# MCU_CU_Schematic.net
KiCad netlist of a schematic drawn in Altium Designer
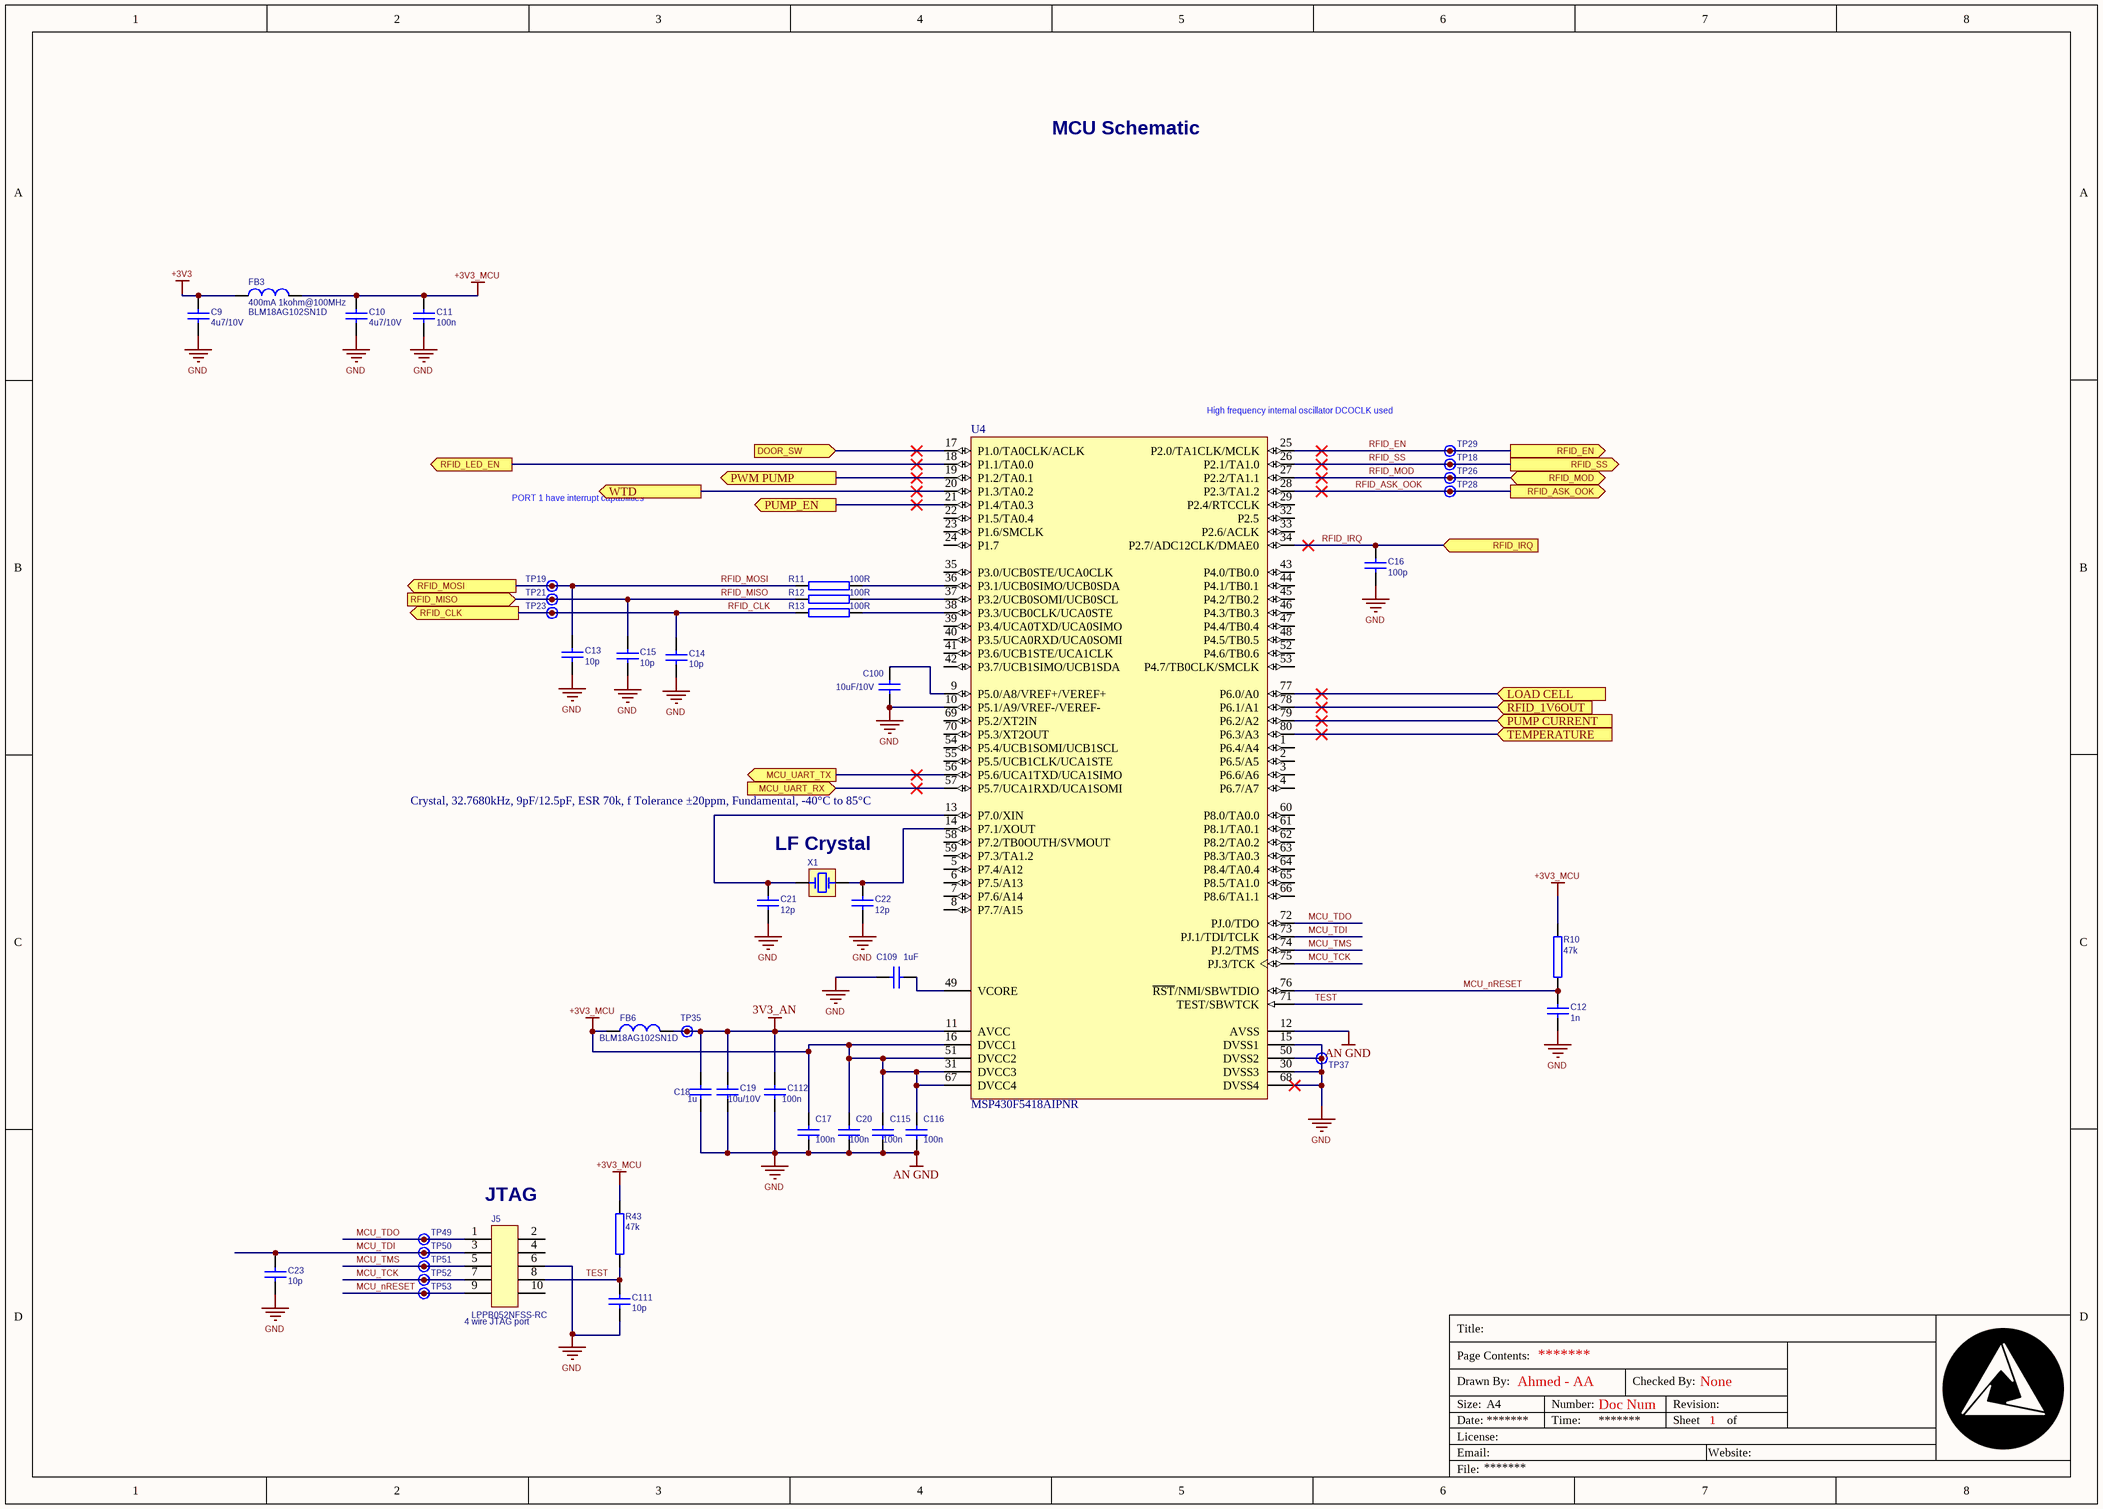
[diagram p0: MCU_CU Schematic.SchDoc]

(export (version "E")
  (design (tool "Eeschema 10.0.6"))
  (components
    (comp (ref "C9")
      (value "4u7/10V")
      (footprint "CAPC1608X09N(0603)")
      (description "Capacitor, Ceramic, 10V, ±10%, X5R, -55°C to 125°C")
      (fields (field (name "02 PART NUMBER") "CC0603KRX5R6BB475") (field (name "12 AUTHOR") "K.Sukumar"))
      (libsource (lib "Ingenuity Master Capacitor Schematic Library") (part "CC0603KRX5R6BB475"))
    )
    (comp (ref "C10")
      (value "4u7/10V")
      (footprint "CAPC1608X09N(0603)")
      (description "Capacitor, Ceramic, 10V, ±10%, X5R, -55°C to 125°C")
      (fields (field (name "02 PART NUMBER") "CC0603KRX5R6BB475") (field (name "12 AUTHOR") "K.Sukumar"))
      (libsource (lib "Ingenuity Master Capacitor Schematic Library") (part "CC0603KRX5R6BB475"))
    )
    (comp (ref "C11")
      (value "100n")
      (footprint "CAPC1608X09N(0603)")
      (description "Capacitor, Ceramic, 50V, ±10%, X7R, -55°C to 125°C")
      (fields (field (name "02 PART NUMBER") "GRM188R71H104KA93D") (field (name "12 AUTHOR") "D.Grace"))
      (libsource (lib "Ingenuity Master Capacitor Schematic Library") (part "GRM188R71H104KA93D"))
    )
    (comp (ref "C12")
      (value "1n")
      (footprint "CAPC1608X09N(0603)")
      (description "Capacitor, Ceramic, 50V, ±5%, C0G NP0, -55°C to 125°C")
      (fields (field (name "02 PART NUMBER") "GRM1885C1H102JA01D") (field (name "12 AUTHOR") "D.Grace"))
      (libsource (lib "Ingenuity Master Capacitor Schematic Library") (part "GRM1885C1H102JA01D"))
    )
    (comp (ref "C13")
      (value "10p")
      (footprint "CAPC1608X09N(0603)")
      (description "Capacitor, Ceramic, 50V, ±5%, NP0, -55°C to 125°C")
      (fields (field (name "02 PART NUMBER") "GQM1885C1H100JB01D") (field (name "12 AUTHOR") "M.Fineschi"))
      (libsource (lib "D0001310 Trophon EPR GUI Carrier Board Schematic Library (1_0)") (part "GQM1885C1H100JB01D"))
    )
    (comp (ref "C14")
      (value "10p")
      (footprint "CAPC1608X09N(0603)")
      (description "Capacitor, Ceramic, 50V, ±5%, NP0, -55°C to 125°C")
      (fields (field (name "02 PART NUMBER") "GQM1885C1H100JB01D") (field (name "12 AUTHOR") "M.Fineschi"))
      (libsource (lib "D0001310 Trophon EPR GUI Carrier Board Schematic Library (1_0)") (part "GQM1885C1H100JB01D"))
    )
    (comp (ref "C15")
      (value "10p")
      (footprint "CAPC1608X09N(0603)")
      (description "Capacitor, Ceramic, 50V, ±5%, NP0, -55°C to 125°C")
      (fields (field (name "02 PART NUMBER") "GQM1885C1H100JB01D") (field (name "12 AUTHOR") "M.Fineschi"))
      (libsource (lib "D0001310 Trophon EPR GUI Carrier Board Schematic Library (1_0)") (part "GQM1885C1H100JB01D"))
    )
    (comp (ref "C16")
      (value "100p")
      (footprint "CAPC1608X09N(0603)")
      (description "Capacitor, Ceramic, 50V, ±5%, C0G NP0, -55°C to 125°C")
      (fields (field (name "02 PART NUMBER") "GRM1885C1H101JA01D") (field (name "12 AUTHOR") "D.Grace"))
      (libsource (lib "Ingenuity Master Capacitor Schematic Library") (part "GRM1885C1H101JA01D"))
    )
    (comp (ref "C17")
      (value "100n")
      (footprint "CAPC1608X09N(0603)")
      (description "Capacitor, Ceramic, 50V, ±10%, X7R, -55°C to 125°C")
      (fields (field (name "02 PART NUMBER") "GRM188R71H104KA93D") (field (name "12 AUTHOR") "D.Grace"))
      (libsource (lib "Ingenuity Master Capacitor Schematic Library") (part "GRM188R71H104KA93D"))
    )
    (comp (ref "C18")
      (value "1u")
      (footprint "CAPC1608X09N(0603)")
      (description "Capacitor, Ceramic, 25V, ±10%, X7R, -55°C to 125°C")
      (fields (field (name "02 PART NUMBER") "GRM188R71E105KA12D") (field (name "12 AUTHOR") "D.Grace"))
      (libsource (lib "Ingenuity Master Capacitor Schematic Library") (part "GRM188R71E105KA12D"))
    )
    (comp (ref "C19")
      (value "10u/10V")
      (footprint "CAPC1608X09N(0603)")
      (description "Capacitor, Ceramic, 10V, ±20%, X5R, -55°C to 85°C")
      (fields (field (name "02 PART NUMBER") "C1608X5R1A106M080AC") (field (name "12 AUTHOR") "K.Sukumar"))
      (libsource (lib "Ingenuity Master Capacitor Schematic Library") (part "C1608X5R1A106M080AC"))
    )
    (comp (ref "C20")
      (value "100n")
      (footprint "CAPC1608X09N(0603)")
      (description "Capacitor, Ceramic, 50V, ±10%, X7R, -55°C to 125°C")
      (fields (field (name "02 PART NUMBER") "GRM188R71H104KA93D") (field (name "12 AUTHOR") "D.Grace"))
      (libsource (lib "Ingenuity Master Capacitor Schematic Library") (part "GRM188R71H104KA93D"))
    )
    (comp (ref "C21")
      (value "12p")
      (footprint "CAPC1608X09N(0603)")
      (description "Capacitor, Ceramic, 50V, ±5%, C0G NP0, -55°C to 125°C")
      (fields (field (name "02 PART NUMBER") "GRM1885C1H120JA01D") (field (name "12 AUTHOR") "D.Grace"))
      (libsource (lib "<Company> Vault") (part "CMP-007-0078-1"))
    )
    (comp (ref "C22")
      (value "12p")
      (footprint "CAPC1608X09N(0603)")
      (description "Capacitor, Ceramic, 50V, ±5%, C0G NP0, -55°C to 125°C")
      (fields (field (name "02 PART NUMBER") "GRM1885C1H120JA01D") (field (name "12 AUTHOR") "D.Grace"))
      (libsource (lib "<Company> Vault") (part "CMP-007-0078-1"))
    )
    (comp (ref "C23")
      (value "10p")
      (footprint "CAPC1608X09N(0603)")
      (description "Capacitor, Ceramic, 50V, ±5%, NP0, -55°C to 125°C")
      (fields (field (name "02 PART NUMBER") "GQM1885C1H100JB01D") (field (name "12 AUTHOR") "M.Fineschi"))
      (libsource (lib "D0001310 Trophon EPR GUI Carrier Board Schematic Library (1_0)") (part "GQM1885C1H100JB01D"))
    )
    (comp (ref "C100")
      (value "10uF/10V")
      (footprint "CAPC1608X09N(0603)")
      (description "Capacitor, Ceramic, 10V, ±10%, X5R, -55°C to 125°C")
      (fields (field (name "02 PART NUMBER") "CC0603KRX5R6BB475") (field (name "12 AUTHOR") "K.Sukumar"))
      (libsource (lib "RFID Board") (part "CC0603KRX5R6BB475"))
    )
    (comp (ref "C109")
      (value "1uF")
      (footprint "CAPC1608X09N(0603)")
      (description "Capacitor, Ceramic, 10V, ±10%, X5R, -55°C to 125°C")
      (fields (field (name "02 PART NUMBER") "CC0603KRX5R6BB475") (field (name "12 AUTHOR") "K.Sukumar"))
      (libsource (lib "RFID Board") (part "CC0603KRX5R6BB475"))
    )
    (comp (ref "C111")
      (value "10p")
      (footprint "CAPC1608X09N(0603)")
      (description "Capacitor, Ceramic, 50V, ±5%, NP0, -55°C to 125°C")
      (fields (field (name "02 PART NUMBER") "GQM1885C1H100JB01D") (field (name "12 AUTHOR") "M.Fineschi"))
      (libsource (lib "D0001310 Trophon EPR GUI Carrier Board Schematic Library (1_0)") (part "GQM1885C1H100JB01D"))
    )
    (comp (ref "C112")
      (value "100n")
      (footprint "CAPC1608X09N(0603)")
      (description "Capacitor, Ceramic, 50V, ±10%, X7R, -55°C to 125°C")
      (fields (field (name "02 PART NUMBER") "GRM188R71H104KA93D") (field (name "12 AUTHOR") "D.Grace"))
      (libsource (lib "Ingenuity Master Capacitor Schematic Library") (part "GRM188R71H104KA93D"))
    )
    (comp (ref "C115")
      (value "100n")
      (footprint "CAPC1608X09N(0603)")
      (description "Capacitor, Ceramic, 50V, ±10%, X7R, -55°C to 125°C")
      (fields (field (name "02 PART NUMBER") "GRM188R71H104KA93D") (field (name "12 AUTHOR") "D.Grace"))
      (libsource (lib "Ingenuity Master Capacitor Schematic Library") (part "GRM188R71H104KA93D"))
    )
    (comp (ref "C116")
      (value "100n")
      (footprint "CAPC1608X09N(0603)")
      (description "Capacitor, Ceramic, 50V, ±10%, X7R, -55°C to 125°C")
      (fields (field (name "02 PART NUMBER") "GRM188R71H104KA93D") (field (name "12 AUTHOR") "D.Grace"))
      (libsource (lib "Ingenuity Master Capacitor Schematic Library") (part "GRM188R71H104KA93D"))
    )
    (comp (ref "FB3")
      (value "400mA 1kohm@100MHz")
      (footprint "RESC1608X06N")
      (description "Ferrite Bead, 1kohm@100MHz, 400mA, 500mohm, -55 to 125C")
      (fields (field (name "02 PART NUMBER") "BLM18AG102SN1D") (field (name "12 AUTHOR") "M.Fineschi"))
      (libsource (lib "D0000174 Puck Charger Schematic Library (1_6)") (part "BLM18AG102SN1D"))
    )
    (comp (ref "FB6")
      (value "400mA 1kohm@100MHz")
      (footprint "RESC1608X06N")
      (description "Ferrite Bead, 1kohm@100MHz, 400mA, 500mohm, -55 to 125C")
      (fields (field (name "02 PART NUMBER") "BLM18AG102SN1D") (field (name "12 AUTHOR") "M.Fineschi"))
      (libsource (lib "D0000174 Puck Charger Schematic Library (1_6)") (part "BLM18AG102SN1D"))
    )
    (comp (ref "J5")
      (value "LPPB052NFSS-RC")
      (footprint "2x 5, 1.27mm Pitch")
      (description "Socket,  Female, 2x5, 10 POS, Pitch 1.27mm")
      (fields (field (name "12 AUTHOR") "K.Sukumar"))
      (libsource (lib "VSS Windscreen Unit Schematic library") (part "LPPB052NFSS-RC"))
    )
    (comp (ref "R10")
      (value "47k")
      (footprint "RESC1608X06N(0603)")
      (description "Resistor, Thick Film, 0.1W, ±1%, ±100ppm/°C")
      (fields
        (field (name "02 PART NUMBER") "RC0603FR-0747KL")
        (field (name "13 REVIEWED BY") "P.Moutzouris")
        (field (name "12 AUTHOR") "D.Grace")
      )
      (libsource (lib "Ingenuity Master Resistor 0603 Schematic Library") (part "RC0603FR-0747KL"))
    )
    (comp (ref "R11")
      (value "100R")
      (footprint "RESC1608X06N(0603)")
      (description "Resistor, Thick Film, 0.1W, ±1%, ±100ppm/°C")
      (fields
        (field (name "02 PART NUMBER") "RC0603FR-07100RL")
        (field (name "13 REVIEWED BY") "P.Moutzouris")
        (field (name "12 AUTHOR") "D.Grace")
      )
      (libsource (lib "Ingenuity Master Resistor 0603 Schematic Library") (part "RC0603FR-07100RL"))
    )
    (comp (ref "R12")
      (value "100R")
      (footprint "RESC1608X06N(0603)")
      (description "Resistor, Thick Film, 0.1W, ±1%, ±100ppm/°C")
      (fields
        (field (name "02 PART NUMBER") "RC0603FR-07100RL")
        (field (name "13 REVIEWED BY") "P.Moutzouris")
        (field (name "12 AUTHOR") "D.Grace")
      )
      (libsource (lib "Ingenuity Master Resistor 0603 Schematic Library") (part "RC0603FR-07100RL"))
    )
    (comp (ref "R13")
      (value "100R")
      (footprint "RESC1608X06N(0603)")
      (description "Resistor, Thick Film, 0.1W, ±1%, ±100ppm/°C")
      (fields
        (field (name "02 PART NUMBER") "RC0603FR-07100RL")
        (field (name "13 REVIEWED BY") "P.Moutzouris")
        (field (name "12 AUTHOR") "D.Grace")
      )
      (libsource (lib "Ingenuity Master Resistor 0603 Schematic Library") (part "RC0603FR-07100RL"))
    )
    (comp (ref "R43")
      (value "47k")
      (footprint "RESC1608X06N(0603)")
      (description "Resistor, Thick Film, 0.1W, ±1%, ±100ppm/°C")
      (fields
        (field (name "02 PART NUMBER") "RC0603FR-0747KL")
        (field (name "13 REVIEWED BY") "P.Moutzouris")
        (field (name "12 AUTHOR") "D.Grace")
      )
      (libsource (lib "Ingenuity Master Resistor 0603 Schematic Library") (part "RC0603FR-0747KL"))
    )
    (comp (ref "TP18")
      (value "LFX_P")
      (footprint "Test Point 1mm")
      (description "Test Point")
      (fields (field (name "12 AUTHOR") "D.Grace"))
      (libsource (lib "Mesh Nebuliser Schematic Library") (part "Test Point"))
    )
    (comp (ref "TP19")
      (value "LFX_P")
      (footprint "Test Point 1mm")
      (description "Test Point")
      (fields (field (name "12 AUTHOR") "D.Grace"))
      (libsource (lib "Mesh Nebuliser Schematic Library") (part "Test Point"))
    )
    (comp (ref "TP21")
      (value "LFX_P")
      (footprint "Test Point 1mm")
      (description "Test Point")
      (fields (field (name "12 AUTHOR") "D.Grace"))
      (libsource (lib "Mesh Nebuliser Schematic Library") (part "Test Point"))
    )
    (comp (ref "TP23")
      (value "LFX_P")
      (footprint "Test Point 1mm")
      (description "Test Point")
      (fields (field (name "12 AUTHOR") "D.Grace"))
      (libsource (lib "Mesh Nebuliser Schematic Library") (part "Test Point"))
    )
    (comp (ref "TP26")
      (value "LFX_P")
      (footprint "Test Point 1mm")
      (description "Test Point")
      (fields (field (name "12 AUTHOR") "D.Grace"))
      (libsource (lib "Mesh Nebuliser Schematic Library") (part "Test Point"))
    )
    (comp (ref "TP28")
      (value "LFX_P")
      (footprint "Test Point 1mm")
      (description "Test Point")
      (fields (field (name "12 AUTHOR") "D.Grace"))
      (libsource (lib "Mesh Nebuliser Schematic Library") (part "Test Point"))
    )
    (comp (ref "TP29")
      (value "LFX_P")
      (footprint "Test Point 1mm")
      (description "Test Point")
      (fields (field (name "12 AUTHOR") "D.Grace"))
      (libsource (lib "Mesh Nebuliser Schematic Library") (part "Test Point"))
    )
    (comp (ref "TP35")
      (value "LFX_P")
      (footprint "Test Point 1mm")
      (description "Test Point")
      (fields (field (name "12 AUTHOR") "D.Grace"))
      (libsource (lib "Mesh Nebuliser Schematic Library") (part "Test Point"))
    )
    (comp (ref "TP37")
      (value "LFX_P")
      (footprint "Test Point 1mm")
      (description "Test Point")
      (fields (field (name "12 AUTHOR") "D.Grace"))
      (libsource (lib "Mesh Nebuliser Schematic Library") (part "Test Point"))
    )
    (comp (ref "TP49")
      (value "TDO")
      (footprint "Test Point 1mm")
      (description "Test Point")
      (fields (field (name "12 AUTHOR") "D.Grace"))
      (libsource (lib "Mesh Nebuliser Schematic Library") (part "Test Point"))
    )
    (comp (ref "TP50")
      (value "TDO")
      (footprint "Test Point 1mm")
      (description "Test Point")
      (fields (field (name "12 AUTHOR") "D.Grace"))
      (libsource (lib "Mesh Nebuliser Schematic Library") (part "Test Point"))
    )
    (comp (ref "TP51")
      (value "TDO")
      (footprint "Test Point 1mm")
      (description "Test Point")
      (fields (field (name "12 AUTHOR") "D.Grace"))
      (libsource (lib "Mesh Nebuliser Schematic Library") (part "Test Point"))
    )
    (comp (ref "TP52")
      (value "TDO")
      (footprint "Test Point 1mm")
      (description "Test Point")
      (fields (field (name "12 AUTHOR") "D.Grace"))
      (libsource (lib "Mesh Nebuliser Schematic Library") (part "Test Point"))
    )
    (comp (ref "TP53")
      (value "TDO")
      (footprint "Test Point 1mm")
      (description "Test Point")
      (fields (field (name "12 AUTHOR") "D.Grace"))
      (libsource (lib "Mesh Nebuliser Schematic Library") (part "Test Point"))
    )
    (comp (ref "U4")
      (value "MSP430F5418AIPNR")
      (footprint "PN0080A_L")
      (fields (field (name "MANUFACTURER") "Texas Instruments"))
      (libsource (lib "Altium Content Vault") (part "CMP-0365-00449-2"))
    )
    (comp (ref "X1")
      (value "CM315D32768DZCT")
      (footprint "CM315D32768DZCT")
      (description "Crystal, 32.7680kHz, 9pF/12.5pF, ESR 70k, f Tolerance ±20ppm, Fundamental, -40°C to 85°C")
      (fields
        (field (name "03 DESCRIPTION") "Crystal, 32.7680kHz, 9pF/12.5pF, ESR 70k, f Tolerance ±20ppm, Fundamental, -40°C to 85°C")
        (field (name "12 AUTHOR") "D.Grace")
      )
      (libsource (lib "<Company> Vault") (part "CMP-007-0044-1"))
    )
  )
  (nets
    (net (code "1") (name "+3V3") (class "Default")
      (node (ref "C9") (pin "2") (pinfunction "2_2") (pintype "passive"))
      (node (ref "FB3") (pin "1") (pinfunction "1_1") (pintype "passive"))
    )
    (net (code "2") (name "+3V3_MCU") (class "Default")
      (node (ref "C10") (pin "2") (pinfunction "2_2") (pintype "passive"))
      (node (ref "C11") (pin "2") (pinfunction "2_2") (pintype "passive"))
      (node (ref "C115") (pin "2") (pinfunction "2_2") (pintype "passive"))
      (node (ref "C116") (pin "2") (pinfunction "2_2") (pintype "passive"))
      (node (ref "C17") (pin "2") (pinfunction "2_2") (pintype "passive"))
      (node (ref "C20") (pin "2") (pinfunction "2_2") (pintype "passive"))
      (node (ref "FB3") (pin "2") (pinfunction "2_2") (pintype "passive"))
      (node (ref "FB6") (pin "1") (pinfunction "1_1") (pintype "passive"))
      (node (ref "R10") (pin "1") (pintype "passive"))
      (node (ref "R43") (pin "1") (pintype "passive"))
      (node (ref "U4") (pin "16") (pinfunction "DVCC1_16") (pintype "power_in"))
      (node (ref "U4") (pin "31") (pinfunction "DVCC3_31") (pintype "power_in"))
      (node (ref "U4") (pin "51") (pinfunction "DVCC2_51") (pintype "power_in"))
      (node (ref "U4") (pin "67") (pinfunction "DVCC4_67") (pintype "power_in"))
    )
    (net (code "3") (name "/DOOR_SW") (class "Default")
      (node (ref "U4") (pin "17") (pinfunction "P1.0/TA0CLK/ACLK_17") (pintype "bidirectional"))
    )
    (net (code "4") (name "/LOAD CELL") (class "Default")
      (node (ref "U4") (pin "77") (pinfunction "P6.0/A0_77") (pintype "bidirectional"))
    )
    (net (code "5") (name "/MCU_TCK") (class "Default")
      (node (ref "J5") (pin "7") (pinfunction "7_7") (pintype "passive"))
      (node (ref "TP52") (pin "TP") (pinfunction "TP_TP") (pintype "passive"))
      (node (ref "U4") (pin "75") (pinfunction "PJ.3/TCK_75") (pintype "bidirectional"))
    )
    (net (code "6") (name "/MCU_TDI") (class "Default")
      (node (ref "C23") (pin "1") (pinfunction "1_1") (pintype "passive"))
      (node (ref "J5") (pin "3") (pinfunction "3_3") (pintype "passive"))
      (node (ref "TP50") (pin "TP") (pinfunction "TP_TP") (pintype "passive"))
      (node (ref "U4") (pin "73") (pinfunction "PJ.1/TDI/TCLK_73") (pintype "bidirectional"))
    )
    (net (code "7") (name "/MCU_TDO") (class "Default")
      (node (ref "J5") (pin "1") (pinfunction "1_1") (pintype "passive"))
      (node (ref "TP49") (pin "TP") (pinfunction "TP_TP") (pintype "passive"))
      (node (ref "U4") (pin "72") (pinfunction "PJ.0/TDO_72") (pintype "bidirectional"))
    )
    (net (code "8") (name "/MCU_TMS") (class "Default")
      (node (ref "J5") (pin "5") (pinfunction "5_5") (pintype "passive"))
      (node (ref "TP51") (pin "TP") (pinfunction "TP_TP") (pintype "passive"))
      (node (ref "U4") (pin "74") (pinfunction "PJ.2/TMS_74") (pintype "bidirectional"))
    )
    (net (code "9") (name "/MCU_UART_RX") (class "Default")
      (node (ref "U4") (pin "57") (pinfunction "P5.7/UCA1RXD/UCA1SOMI_57") (pintype "bidirectional"))
    )
    (net (code "10") (name "/MCU_UART_TX") (class "Default")
      (node (ref "U4") (pin "56") (pinfunction "P5.6/UCA1TXD/UCA1SIMO_56") (pintype "bidirectional"))
    )
    (net (code "11") (name "/MCU_nRESET") (class "Default")
      (node (ref "C12") (pin "2") (pinfunction "2_2") (pintype "passive"))
      (node (ref "J5") (pin "9") (pinfunction "9_9") (pintype "passive"))
      (node (ref "R10") (pin "2") (pintype "passive"))
      (node (ref "TP53") (pin "TP") (pinfunction "TP_TP") (pintype "passive"))
      (node (ref "U4") (pin "76") (pinfunction "~{RST}/NMI/SBWTDIO_76") (pintype "bidirectional"))
    )
    (net (code "12") (name "/PUMP CURRENT") (class "Default")
      (node (ref "U4") (pin "79") (pinfunction "P6.2/A2_79") (pintype "bidirectional"))
    )
    (net (code "13") (name "/PUMP_EN") (class "Default")
      (node (ref "U4") (pin "21") (pinfunction "P1.4/TA0.3_21") (pintype "bidirectional"))
    )
    (net (code "14") (name "/PWM PUMP") (class "Default")
      (node (ref "U4") (pin "19") (pinfunction "P1.2/TA0.1_19") (pintype "bidirectional"))
    )
    (net (code "15") (name "/RFID_1V6OUT") (class "Default")
      (node (ref "U4") (pin "78") (pinfunction "P6.1/A1_78") (pintype "bidirectional"))
    )
    (net (code "16") (name "/RFID_ASK_OOK") (class "Default")
      (node (ref "TP28") (pin "TP") (pinfunction "TP_TP") (pintype "passive"))
      (node (ref "U4") (pin "28") (pinfunction "P2.3/TA1.2_28") (pintype "bidirectional"))
    )
    (net (code "17") (name "/RFID_CLK") (class "Default")
      (node (ref "C14") (pin "1") (pinfunction "1_1") (pintype "passive"))
      (node (ref "R13") (pin "2") (pintype "passive"))
      (node (ref "TP23") (pin "TP") (pinfunction "TP_TP") (pintype "passive"))
    )
    (net (code "18") (name "/RFID_EN") (class "Default")
      (node (ref "TP29") (pin "TP") (pinfunction "TP_TP") (pintype "passive"))
      (node (ref "U4") (pin "25") (pinfunction "P2.0/TA1CLK/MCLK_25") (pintype "bidirectional"))
    )
    (net (code "19") (name "/RFID_IRQ") (class "Default")
      (node (ref "C16") (pin "2") (pinfunction "2_2") (pintype "passive"))
      (node (ref "U4") (pin "34") (pinfunction "P2.7/ADC12CLK/DMAE0_34") (pintype "bidirectional"))
    )
    (net (code "20") (name "/RFID_LED_EN") (class "Default")
      (node (ref "U4") (pin "18") (pinfunction "P1.1/TA0.0_18") (pintype "bidirectional"))
    )
    (net (code "21") (name "/RFID_MISO") (class "Default")
      (node (ref "C15") (pin "1") (pinfunction "1_1") (pintype "passive"))
      (node (ref "R12") (pin "2") (pintype "passive"))
      (node (ref "TP21") (pin "TP") (pinfunction "TP_TP") (pintype "passive"))
    )
    (net (code "22") (name "/RFID_MOD") (class "Default")
      (node (ref "TP26") (pin "TP") (pinfunction "TP_TP") (pintype "passive"))
      (node (ref "U4") (pin "27") (pinfunction "P2.2/TA1.1_27") (pintype "bidirectional"))
    )
    (net (code "23") (name "/RFID_MOSI") (class "Default")
      (node (ref "C13") (pin "1") (pinfunction "1_1") (pintype "passive"))
      (node (ref "R11") (pin "2") (pintype "passive"))
      (node (ref "TP19") (pin "TP") (pinfunction "TP_TP") (pintype "passive"))
    )
    (net (code "24") (name "/RFID_SS") (class "Default")
      (node (ref "TP18") (pin "TP") (pinfunction "TP_TP") (pintype "passive"))
      (node (ref "U4") (pin "26") (pinfunction "P2.1/TA1.0_26") (pintype "bidirectional"))
    )
    (net (code "25") (name "/TEMPERATURE") (class "Default")
      (node (ref "U4") (pin "80") (pinfunction "P6.3/A3_80") (pintype "bidirectional"))
    )
    (net (code "26") (name "/TEST") (class "Default")
      (node (ref "C111") (pin "1") (pinfunction "1_1") (pintype "passive"))
      (node (ref "J5") (pin "8") (pinfunction "8_8") (pintype "passive"))
      (node (ref "R43") (pin "2") (pintype "passive"))
      (node (ref "U4") (pin "71") (pinfunction "TEST/SBWTCK_71") (pintype "input"))
    )
    (net (code "27") (name "/WTD") (class "Default")
      (node (ref "U4") (pin "20") (pinfunction "P1.3/TA0.2_20") (pintype "bidirectional"))
    )
    (net (code "28") (name "3V3_AN") (class "Default")
      (node (ref "C112") (pin "2") (pinfunction "2_2") (pintype "passive"))
      (node (ref "C18") (pin "2") (pinfunction "2_2") (pintype "passive"))
      (node (ref "C19") (pin "2") (pinfunction "2_2") (pintype "passive"))
      (node (ref "FB6") (pin "2") (pinfunction "2_2") (pintype "passive"))
      (node (ref "TP35") (pin "TP") (pinfunction "TP_TP") (pintype "passive"))
      (node (ref "U4") (pin "11") (pinfunction "AVCC_11") (pintype "power_in"))
    )
    (net (code "29") (name "AN GND") (class "Default")
      (node (ref "C10") (pin "1") (pinfunction "1_1") (pintype "passive"))
      (node (ref "C100") (pin "1") (pinfunction "1_1") (pintype "passive"))
      (node (ref "C109") (pin "2") (pinfunction "2_2") (pintype "passive"))
      (node (ref "C11") (pin "1") (pinfunction "1_1") (pintype "passive"))
      (node (ref "C111") (pin "2") (pinfunction "2_2") (pintype "passive"))
      (node (ref "C112") (pin "1") (pinfunction "1_1") (pintype "passive"))
      (node (ref "C115") (pin "1") (pinfunction "1_1") (pintype "passive"))
      (node (ref "C116") (pin "1") (pinfunction "1_1") (pintype "passive"))
      (node (ref "C12") (pin "1") (pinfunction "1_1") (pintype "passive"))
      (node (ref "C13") (pin "2") (pinfunction "2_2") (pintype "passive"))
      (node (ref "C14") (pin "2") (pinfunction "2_2") (pintype "passive"))
      (node (ref "C15") (pin "2") (pinfunction "2_2") (pintype "passive"))
      (node (ref "C16") (pin "1") (pinfunction "1_1") (pintype "passive"))
      (node (ref "C17") (pin "1") (pinfunction "1_1") (pintype "passive"))
      (node (ref "C18") (pin "1") (pinfunction "1_1") (pintype "passive"))
      (node (ref "C19") (pin "1") (pinfunction "1_1") (pintype "passive"))
      (node (ref "C20") (pin "1") (pinfunction "1_1") (pintype "passive"))
      (node (ref "C21") (pin "1") (pinfunction "1_1") (pintype "passive"))
      (node (ref "C22") (pin "1") (pinfunction "1_1") (pintype "passive"))
      (node (ref "C23") (pin "2") (pinfunction "2_2") (pintype "passive"))
      (node (ref "C9") (pin "1") (pinfunction "1_1") (pintype "passive"))
      (node (ref "J5") (pin "6") (pinfunction "6_6") (pintype "passive"))
      (node (ref "TP37") (pin "TP") (pinfunction "TP_TP") (pintype "passive"))
      (node (ref "U4") (pin "10") (pinfunction "P5.1/A9/VREF-/VEREF-_10") (pintype "bidirectional"))
      (node (ref "U4") (pin "12") (pinfunction "AVSS_12") (pintype "power_in"))
      (node (ref "U4") (pin "15") (pinfunction "DVSS1_15") (pintype "power_in"))
      (node (ref "U4") (pin "30") (pinfunction "DVSS3_30") (pintype "power_in"))
      (node (ref "U4") (pin "50") (pinfunction "DVSS2_50") (pintype "power_in"))
      (node (ref "U4") (pin "68") (pinfunction "DVSS4_68") (pintype "power_in"))
    )
    (net (code "30") (name "Net-(U4-P3.1{slash}UCB0SIMO{slash}UCB0SDA)") (class "Default")
      (node (ref "R11") (pin "1") (pintype "passive"))
      (node (ref "U4") (pin "36") (pinfunction "P3.1/UCB0SIMO/UCB0SDA_36") (pintype "bidirectional"))
    )
    (net (code "31") (name "Net-(U4-P3.2{slash}UCB0SOMI{slash}UCB0SCL)") (class "Default")
      (node (ref "R12") (pin "1") (pintype "passive"))
      (node (ref "U4") (pin "37") (pinfunction "P3.2/UCB0SOMI/UCB0SCL_37") (pintype "bidirectional"))
    )
    (net (code "32") (name "Net-(U4-P3.3{slash}UCB0CLK{slash}UCA0STE)") (class "Default")
      (node (ref "R13") (pin "1") (pintype "passive"))
      (node (ref "U4") (pin "38") (pinfunction "P3.3/UCB0CLK/UCA0STE_38") (pintype "bidirectional"))
    )
    (net (code "33") (name "Net-(U4-P5.0{slash}A8{slash}VREF+{slash}VEREF+)") (class "Default")
      (node (ref "C100") (pin "2") (pinfunction "2_2") (pintype "passive"))
      (node (ref "U4") (pin "9") (pinfunction "P5.0/A8/VREF+/VEREF+_9") (pintype "bidirectional"))
    )
    (net (code "34") (name "Net-(U4-P7.0{slash}XIN)") (class "Default")
      (node (ref "C21") (pin "2") (pinfunction "2_2") (pintype "passive"))
      (node (ref "U4") (pin "13") (pinfunction "P7.0/XIN_13") (pintype "bidirectional"))
      (node (ref "X1") (pin "1") (pinfunction "HOT_1") (pintype "passive"))
    )
    (net (code "35") (name "Net-(U4-P7.1{slash}XOUT)") (class "Default")
      (node (ref "C22") (pin "2") (pinfunction "2_2") (pintype "passive"))
      (node (ref "U4") (pin "14") (pinfunction "P7.1/XOUT_14") (pintype "bidirectional"))
      (node (ref "X1") (pin "2") (pinfunction "HOT_2") (pintype "passive"))
    )
    (net (code "36") (name "Net-(U4-VCORE)") (class "Default")
      (node (ref "C109") (pin "1") (pinfunction "1_1") (pintype "passive"))
      (node (ref "U4") (pin "49") (pinfunction "VCORE_49") (pintype "passive"))
    )
    (net (code "37") (name "unconnected-(J5-Pad2)") (class "Default")
      (node (ref "J5") (pin "2") (pinfunction "2_2") (pintype "passive"))
    )
    (net (code "38") (name "unconnected-(J5-Pad4)") (class "Default")
      (node (ref "J5") (pin "4") (pinfunction "4_4") (pintype "passive"))
    )
    (net (code "39") (name "unconnected-(J5-Pad10)") (class "Default")
      (node (ref "J5") (pin "10") (pinfunction "10_10") (pintype "passive"))
    )
    (net (code "40") (name "unconnected-(U4-P1.5{slash}TA0.4-Pad22)") (class "Default")
      (node (ref "U4") (pin "22") (pinfunction "P1.5/TA0.4_22") (pintype "bidirectional"))
    )
    (net (code "41") (name "unconnected-(U4-P1.6{slash}SMCLK-Pad23)") (class "Default")
      (node (ref "U4") (pin "23") (pinfunction "P1.6/SMCLK_23") (pintype "bidirectional"))
    )
    (net (code "42") (name "unconnected-(U4-P1.7-Pad24)") (class "Default")
      (node (ref "U4") (pin "24") (pinfunction "P1.7_24") (pintype "bidirectional"))
    )
    (net (code "43") (name "unconnected-(U4-P2.4{slash}RTCCLK-Pad29)") (class "Default")
      (node (ref "U4") (pin "29") (pinfunction "P2.4/RTCCLK_29") (pintype "bidirectional"))
    )
    (net (code "44") (name "unconnected-(U4-P2.5-Pad32)") (class "Default")
      (node (ref "U4") (pin "32") (pinfunction "P2.5_32") (pintype "bidirectional"))
    )
    (net (code "45") (name "unconnected-(U4-P2.6{slash}ACLK-Pad33)") (class "Default")
      (node (ref "U4") (pin "33") (pinfunction "P2.6/ACLK_33") (pintype "bidirectional"))
    )
    (net (code "46") (name "unconnected-(U4-P3.0{slash}UCB0STE{slash}UCA0CLK-Pad35)") (class "Default")
      (node (ref "U4") (pin "35") (pinfunction "P3.0/UCB0STE/UCA0CLK_35") (pintype "bidirectional"))
    )
    (net (code "47") (name "unconnected-(U4-P3.4{slash}UCA0TXD{slash}UCA0SIMO-Pad39)") (class "Default")
      (node (ref "U4") (pin "39") (pinfunction "P3.4/UCA0TXD/UCA0SIMO_39") (pintype "bidirectional"))
    )
    (net (code "48") (name "unconnected-(U4-P3.5{slash}UCA0RXD{slash}UCA0SOMI-Pad40)") (class "Default")
      (node (ref "U4") (pin "40") (pinfunction "P3.5/UCA0RXD/UCA0SOMI_40") (pintype "bidirectional"))
    )
    (net (code "49") (name "unconnected-(U4-P3.6{slash}UCB1STE{slash}UCA1CLK-Pad41)") (class "Default")
      (node (ref "U4") (pin "41") (pinfunction "P3.6/UCB1STE/UCA1CLK_41") (pintype "bidirectional"))
    )
    (net (code "50") (name "unconnected-(U4-P3.7{slash}UCB1SIMO{slash}UCB1SDA-Pad42)") (class "Default")
      (node (ref "U4") (pin "42") (pinfunction "P3.7/UCB1SIMO/UCB1SDA_42") (pintype "bidirectional"))
    )
    (net (code "51") (name "unconnected-(U4-P4.0{slash}TB0.0-Pad43)") (class "Default")
      (node (ref "U4") (pin "43") (pinfunction "P4.0/TB0.0_43") (pintype "bidirectional"))
    )
    (net (code "52") (name "unconnected-(U4-P4.1{slash}TB0.1-Pad44)") (class "Default")
      (node (ref "U4") (pin "44") (pinfunction "P4.1/TB0.1_44") (pintype "bidirectional"))
    )
    (net (code "53") (name "unconnected-(U4-P4.2{slash}TB0.2-Pad45)") (class "Default")
      (node (ref "U4") (pin "45") (pinfunction "P4.2/TB0.2_45") (pintype "bidirectional"))
    )
    (net (code "54") (name "unconnected-(U4-P4.3{slash}TB0.3-Pad46)") (class "Default")
      (node (ref "U4") (pin "46") (pinfunction "P4.3/TB0.3_46") (pintype "bidirectional"))
    )
    (net (code "55") (name "unconnected-(U4-P4.4{slash}TB0.4-Pad47)") (class "Default")
      (node (ref "U4") (pin "47") (pinfunction "P4.4/TB0.4_47") (pintype "bidirectional"))
    )
    (net (code "56") (name "unconnected-(U4-P4.5{slash}TB0.5-Pad48)") (class "Default")
      (node (ref "U4") (pin "48") (pinfunction "P4.5/TB0.5_48") (pintype "bidirectional"))
    )
    (net (code "57") (name "unconnected-(U4-P4.6{slash}TB0.6-Pad52)") (class "Default")
      (node (ref "U4") (pin "52") (pinfunction "P4.6/TB0.6_52") (pintype "bidirectional"))
    )
    (net (code "58") (name "unconnected-(U4-P4.7{slash}TB0CLK{slash}SMCLK-Pad53)") (class "Default")
      (node (ref "U4") (pin "53") (pinfunction "P4.7/TB0CLK/SMCLK_53") (pintype "bidirectional"))
    )
    (net (code "59") (name "unconnected-(U4-P5.2{slash}XT2IN-Pad69)") (class "Default")
      (node (ref "U4") (pin "69") (pinfunction "P5.2/XT2IN_69") (pintype "bidirectional"))
    )
    (net (code "60") (name "unconnected-(U4-P5.3{slash}XT2OUT-Pad70)") (class "Default")
      (node (ref "U4") (pin "70") (pinfunction "P5.3/XT2OUT_70") (pintype "bidirectional"))
    )
    (net (code "61") (name "unconnected-(U4-P5.4{slash}UCB1SOMI{slash}UCB1SCL-Pad54)") (class "Default")
      (node (ref "U4") (pin "54") (pinfunction "P5.4/UCB1SOMI/UCB1SCL_54") (pintype "bidirectional"))
    )
    (net (code "62") (name "unconnected-(U4-P5.5{slash}UCB1CLK{slash}UCA1STE-Pad55)") (class "Default")
      (node (ref "U4") (pin "55") (pinfunction "P5.5/UCB1CLK/UCA1STE_55") (pintype "bidirectional"))
    )
    (net (code "63") (name "unconnected-(U4-P6.4{slash}A4-Pad1)") (class "Default")
      (node (ref "U4") (pin "1") (pinfunction "P6.4/A4_1") (pintype "bidirectional"))
    )
    (net (code "64") (name "unconnected-(U4-P6.5{slash}A5-Pad2)") (class "Default")
      (node (ref "U4") (pin "2") (pinfunction "P6.5/A5_2") (pintype "bidirectional"))
    )
    (net (code "65") (name "unconnected-(U4-P6.6{slash}A6-Pad3)") (class "Default")
      (node (ref "U4") (pin "3") (pinfunction "P6.6/A6_3") (pintype "bidirectional"))
    )
    (net (code "66") (name "unconnected-(U4-P6.7{slash}A7-Pad4)") (class "Default")
      (node (ref "U4") (pin "4") (pinfunction "P6.7/A7_4") (pintype "bidirectional"))
    )
    (net (code "67") (name "unconnected-(U4-P7.2{slash}TB0OUTH{slash}SVMOUT-Pad58)") (class "Default")
      (node (ref "U4") (pin "58") (pinfunction "P7.2/TB0OUTH/SVMOUT_58") (pintype "bidirectional"))
    )
    (net (code "68") (name "unconnected-(U4-P7.3{slash}TA1.2-Pad59)") (class "Default")
      (node (ref "U4") (pin "59") (pinfunction "P7.3/TA1.2_59") (pintype "bidirectional"))
    )
    (net (code "69") (name "unconnected-(U4-P7.4{slash}A12-Pad5)") (class "Default")
      (node (ref "U4") (pin "5") (pinfunction "P7.4/A12_5") (pintype "bidirectional"))
    )
    (net (code "70") (name "unconnected-(U4-P7.5{slash}A13-Pad6)") (class "Default")
      (node (ref "U4") (pin "6") (pinfunction "P7.5/A13_6") (pintype "bidirectional"))
    )
    (net (code "71") (name "unconnected-(U4-P7.6{slash}A14-Pad7)") (class "Default")
      (node (ref "U4") (pin "7") (pinfunction "P7.6/A14_7") (pintype "bidirectional"))
    )
    (net (code "72") (name "unconnected-(U4-P7.7{slash}A15-Pad8)") (class "Default")
      (node (ref "U4") (pin "8") (pinfunction "P7.7/A15_8") (pintype "bidirectional"))
    )
    (net (code "73") (name "unconnected-(U4-P8.0{slash}TA0.0-Pad60)") (class "Default")
      (node (ref "U4") (pin "60") (pinfunction "P8.0/TA0.0_60") (pintype "bidirectional"))
    )
    (net (code "74") (name "unconnected-(U4-P8.1{slash}TA0.1-Pad61)") (class "Default")
      (node (ref "U4") (pin "61") (pinfunction "P8.1/TA0.1_61") (pintype "bidirectional"))
    )
    (net (code "75") (name "unconnected-(U4-P8.2{slash}TA0.2-Pad62)") (class "Default")
      (node (ref "U4") (pin "62") (pinfunction "P8.2/TA0.2_62") (pintype "bidirectional"))
    )
    (net (code "76") (name "unconnected-(U4-P8.3{slash}TA0.3-Pad63)") (class "Default")
      (node (ref "U4") (pin "63") (pinfunction "P8.3/TA0.3_63") (pintype "bidirectional"))
    )
    (net (code "77") (name "unconnected-(U4-P8.4{slash}TA0.4-Pad64)") (class "Default")
      (node (ref "U4") (pin "64") (pinfunction "P8.4/TA0.4_64") (pintype "bidirectional"))
    )
    (net (code "78") (name "unconnected-(U4-P8.5{slash}TA1.0-Pad65)") (class "Default")
      (node (ref "U4") (pin "65") (pinfunction "P8.5/TA1.0_65") (pintype "bidirectional"))
    )
    (net (code "79") (name "unconnected-(U4-P8.6{slash}TA1.1-Pad66)") (class "Default")
      (node (ref "U4") (pin "66") (pinfunction "P8.6/TA1.1_66") (pintype "bidirectional"))
    )
  )
)
